# 06_ETHERNET.net
KiCad netlist of a schematic drawn in Altium Designer
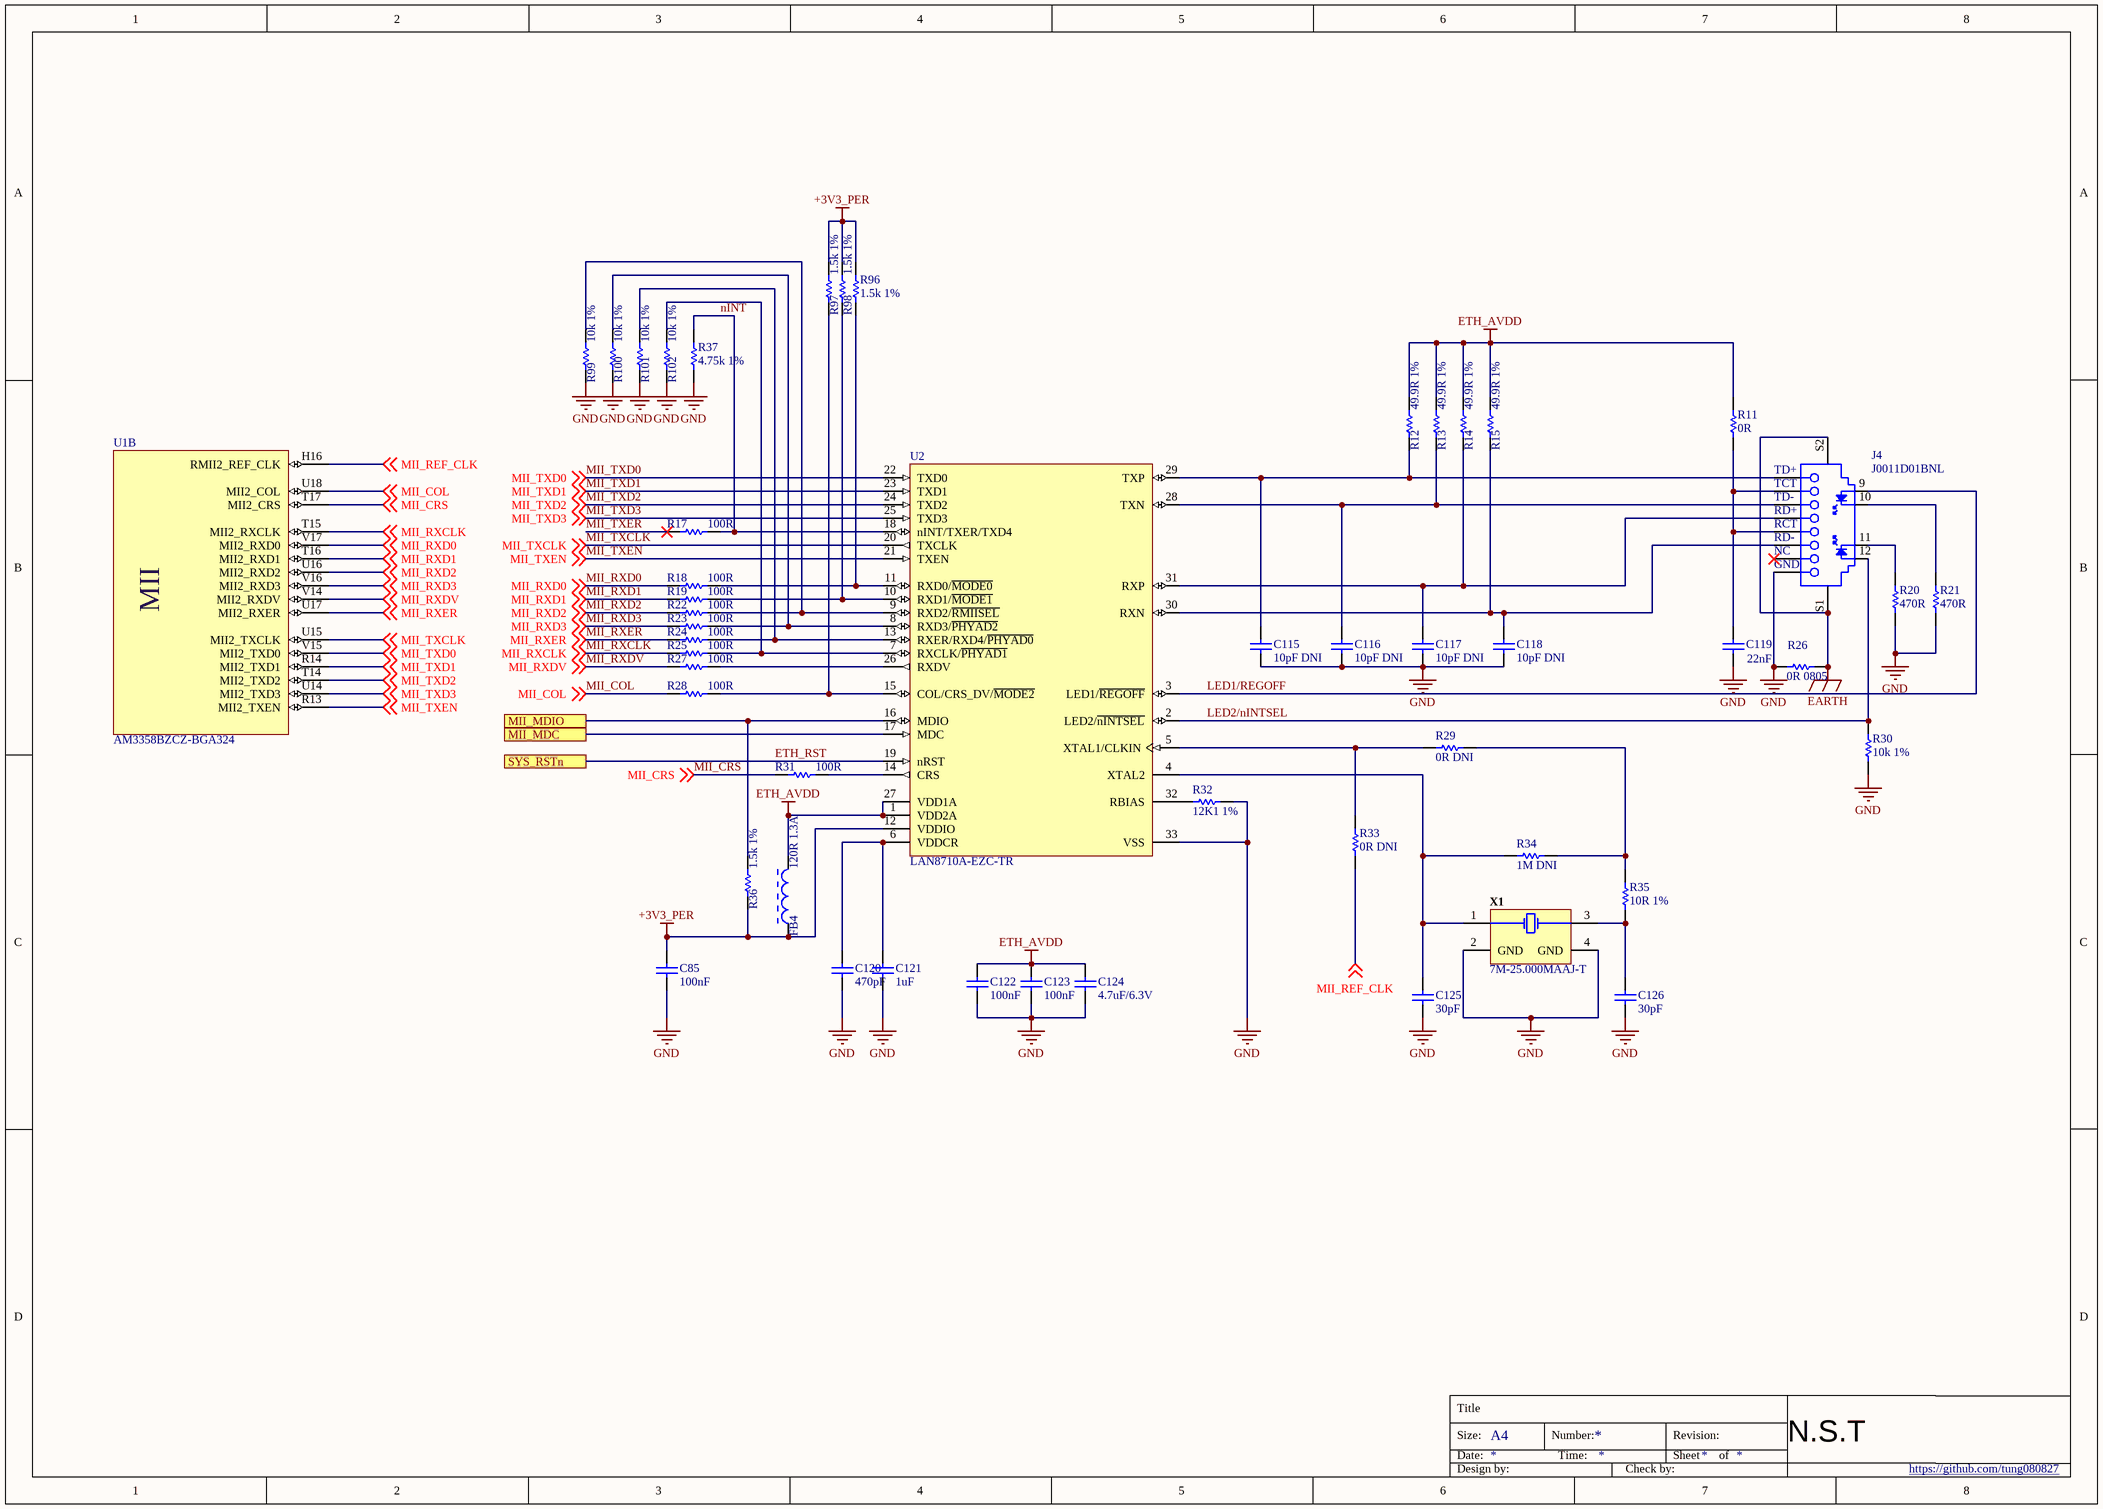
[diagram p0: 06. ETHERNET.SchDoc]

(export (version "E")
  (design (tool "Eeschema 10.0.6"))
  (components
    (comp (ref "C85")
      (value "100nF")
      (footprint "CAPC1005X60X30LL05T10")
      (description "Chip Capacitor, 0.1 uF, +/- 10%, 16 V, -55 to 125 degC, 0402 (1005 Metric), RoHS, Tape and Reel")
      (fields (field (name "VOLTAGE") "16V") (field (name "TOLERANCE") "10%"))
      (libsource (lib "AM3358_DEV_BOARD") (part "CAP-NP-2"))
    )
    (comp (ref "C115")
      (value "10pF DNI")
      (footprint "CAPC1005X60X30LL05T10")
      (fields (field (name "MANUFACTURER") "Murata") (field (name "PART NUMBER") "GRM1555C1E100JA01D"))
      (libsource (lib "AM3358_DEV_BOARD") (part "CAP"))
    )
    (comp (ref "C116")
      (value "10pF DNI")
      (footprint "CAPC1005X60X30LL05T10")
      (fields (field (name "MANUFACTURER") "Murata") (field (name "PART NUMBER") "GRM1555C1E100JA01D"))
      (libsource (lib "AM3358_DEV_BOARD") (part "CAP"))
    )
    (comp (ref "C117")
      (value "10pF DNI")
      (footprint "CAPC1005X60X30LL05T10")
      (fields (field (name "MANUFACTURER") "Murata") (field (name "PART NUMBER") "GRM1555C1E100JA01D"))
      (libsource (lib "AM3358_DEV_BOARD") (part "CAP"))
    )
    (comp (ref "C118")
      (value "10pF DNI")
      (footprint "CAPC1005X60X30LL05T10")
      (fields (field (name "MANUFACTURER") "Murata") (field (name "PART NUMBER") "GRM1555C1E100JA01D"))
      (libsource (lib "AM3358_DEV_BOARD") (part "CAP"))
    )
    (comp (ref "C119")
      (value "22nF")
      (footprint "CAPC1005X60X30LL05T10")
      (fields (field (name "PART NUMBER") "GRM155R71H223KA12D") (field (name "MANUFACTURER") "Murata"))
      (libsource (lib "AM3358_DEV_BOARD") (part "CAP"))
    )
    (comp (ref "C120")
      (value "470pF")
      (footprint "CAPC1005X60X30LL05T10")
      (description "CAP 470pF 50V ±10% 0402 (1005 Metric) Thickness 0.6mm SMD")
      (fields (field (name "TOLERANCE") "Â±10%"))
      (libsource (lib "AM3358_DEV_BOARD") (part "CAP"))
    )
    (comp (ref "C121")
      (value "1uF")
      (footprint "CAPC1005X55X25NL05T10")
      (fields (field (name "PART NUMBER") "GRM155R61A105KE15D") (field (name "MANUFACTURER") "Murata"))
      (libsource (lib "Altium Content Vault") (part "CAP"))
    )
    (comp (ref "C122")
      (value "100nF")
      (footprint "CAPC1005X60X30LL05T10")
      (description "Chip Capacitor, 0.1 uF, +/- 10%, 16 V, -55 to 125 degC, 0402 (1005 Metric), RoHS, Tape and Reel")
      (fields (field (name "VOLTAGE") "16V") (field (name "TOLERANCE") "10%"))
      (libsource (lib "AM3358_DEV_BOARD") (part "CAP-NP-2"))
    )
    (comp (ref "C123")
      (value "100nF")
      (footprint "CAPC1005X60X30LL05T10")
      (description "Chip Capacitor, 0.1 uF, +/- 10%, 16 V, -55 to 125 degC, 0402 (1005 Metric), RoHS, Tape and Reel")
      (fields (field (name "VOLTAGE") "16V") (field (name "TOLERANCE") "10%"))
      (libsource (lib "AM3358_DEV_BOARD") (part "CAP-NP-2"))
    )
    (comp (ref "C124")
      (value "4.7uF/6.3V")
      (footprint "CAPC1005X55X25NL05T10")
      (fields (field (name "PART NUMBER") "GRM155R60J475ME47D") (field (name "MANUFACTURER") "Murata"))
      (libsource (lib "Altium Content Vault") (part "CAP"))
    )
    (comp (ref "C125")
      (value "30pF")
      (footprint "CAPC1005X60X30LL05T10")
      (fields (field (name "PART NUMBER") "GRM1555C1H300JA01D") (field (name "MANUFACTURER") "Murata"))
      (libsource (lib "AM3358_DEV_BOARD") (part "CAP"))
    )
    (comp (ref "C126")
      (value "30pF")
      (footprint "CAPC1005X60X30LL05T10")
      (fields (field (name "PART NUMBER") "GRM1555C1H300JA01D") (field (name "MANUFACTURER") "Murata"))
      (libsource (lib "AM3358_DEV_BOARD") (part "CAP"))
    )
    (comp (ref "FB4")
      (value "120R 1.3A")
      (footprint "MURA-BLM15-CHIP-2_V")
      (fields (field (name "PARTNUMBER") "BLM15PD121SN1D") (field (name "MANUFACTURER") "Murata"))
      (libsource (lib "Altium Content Vault") (part "MURA-FB-2"))
    )
    (comp (ref "J4")
      (value "J0011D01BNL")
      (footprint "J0011D01BNL 1PORT 100 BASE-TX")
      (fields (field (name "MANUFACTURER") "Pulse Electronics"))
      (libsource (lib "AM3358_DEV_BOARD") (part "RJ45-12-2SHLD_F"))
    )
    (comp (ref "R11")
      (value "0R")
      (footprint "RESC1005X40X25LL05T05")
      (fields (field (name "PART NUMBER") "CRCW040210R0FKEDHP") (field (name "MANUFACTURER") "Vishay Dale"))
      (libsource (lib "AM3358_DEV_BOARD") (part "RES"))
    )
    (comp (ref "R12")
      (value "49.9R 1%")
      (footprint "RESC1005X40X25LL05T05")
      (description "Precision Thick Film Chip Resistors")
      (fields (field (name "MANUFACTURER") "Panasonic") (field (name "PART NUMBER") "ERJ-2RKF49R9X"))
      (libsource (lib "AM3358_DEV_BOARD") (part "RES"))
    )
    (comp (ref "R13")
      (value "49.9R 1%")
      (footprint "RESC1005X40X25LL05T05")
      (description "Precision Thick Film Chip Resistors")
      (fields (field (name "MANUFACTURER") "Panasonic") (field (name "PART NUMBER") "ERJ-2RKF49R9X"))
      (libsource (lib "AM3358_DEV_BOARD") (part "RES"))
    )
    (comp (ref "R14")
      (value "49.9R 1%")
      (footprint "RESC1005X40X25LL05T05")
      (description "Precision Thick Film Chip Resistors")
      (fields (field (name "MANUFACTURER") "Panasonic") (field (name "PART NUMBER") "ERJ-2RKF49R9X"))
      (libsource (lib "AM3358_DEV_BOARD") (part "RES"))
    )
    (comp (ref "R15")
      (value "49.9R 1%")
      (footprint "RESC1005X40X25LL05T05")
      (description "Precision Thick Film Chip Resistors")
      (fields (field (name "MANUFACTURER") "Panasonic") (field (name "PART NUMBER") "ERJ-2RKF49R9X"))
      (libsource (lib "AM3358_DEV_BOARD") (part "RES"))
    )
    (comp (ref "R17")
      (value "100R")
      (footprint "RESC1005X40X25LL05T05")
      (fields (field (name "MANUFACTURER") "Panasonic") (field (name "PART NUMBER") "ERJ-2GEJ101X"))
      (libsource (lib "AM3358_DEV_BOARD") (part "RES"))
    )
    (comp (ref "R18")
      (value "100R")
      (footprint "RESC1005X40X25LL05T05")
      (fields (field (name "MANUFACTURER") "Panasonic") (field (name "PART NUMBER") "ERJ-2GEJ101X"))
      (libsource (lib "AM3358_DEV_BOARD") (part "RES"))
    )
    (comp (ref "R19")
      (value "100R")
      (footprint "RESC1005X40X25LL05T05")
      (fields (field (name "MANUFACTURER") "Panasonic") (field (name "PART NUMBER") "ERJ-2GEJ101X"))
      (libsource (lib "AM3358_DEV_BOARD") (part "RES"))
    )
    (comp (ref "R20")
      (value "470R")
      (footprint "RESC1005X40X25LL05T05")
      (fields (field (name "PART NUMBER") "CRCW0603470RFKEA") (field (name "MANUFACTURER") "Vishay Dale"))
      (libsource (lib "AM3358_DEV_BOARD") (part "RES"))
    )
    (comp (ref "R21")
      (value "470R")
      (footprint "RESC1005X40X25LL05T05")
      (fields (field (name "PART NUMBER") "CRCW0603470RFKEA") (field (name "MANUFACTURER") "Vishay Dale"))
      (libsource (lib "AM3358_DEV_BOARD") (part "RES"))
    )
    (comp (ref "R22")
      (value "100R")
      (footprint "RESC1005X40X25LL05T05")
      (fields (field (name "MANUFACTURER") "Panasonic") (field (name "PART NUMBER") "ERJ-2GEJ101X"))
      (libsource (lib "AM3358_DEV_BOARD") (part "RES"))
    )
    (comp (ref "R23")
      (value "100R")
      (footprint "RESC1005X40X25LL05T05")
      (fields (field (name "MANUFACTURER") "Panasonic") (field (name "PART NUMBER") "ERJ-2GEJ101X"))
      (libsource (lib "AM3358_DEV_BOARD") (part "RES"))
    )
    (comp (ref "R24")
      (value "100R")
      (footprint "RESC1005X40X25LL05T05")
      (fields (field (name "MANUFACTURER") "Panasonic") (field (name "PART NUMBER") "ERJ-2GEJ101X"))
      (libsource (lib "AM3358_DEV_BOARD") (part "RES"))
    )
    (comp (ref "R25")
      (value "100R")
      (footprint "RESC1005X40X25LL05T05")
      (fields (field (name "MANUFACTURER") "Panasonic") (field (name "PART NUMBER") "ERJ-2GEJ101X"))
      (libsource (lib "AM3358_DEV_BOARD") (part "RES"))
    )
    (comp (ref "R26")
      (value "0R 0805")
      (footprint "RESC2013X50X30LL20T20")
      (fields (field (name "MANUFACTURER") "Vishay Dale") (field (name "PART NUMBER") "CRCW08050000Z0EA"))
      (libsource (lib "Altium Content Vault") (part "RES"))
    )
    (comp (ref "R27")
      (value "100R")
      (footprint "RESC1005X40X25LL05T05")
      (fields (field (name "MANUFACTURER") "Panasonic") (field (name "PART NUMBER") "ERJ-2GEJ101X"))
      (libsource (lib "AM3358_DEV_BOARD") (part "RES"))
    )
    (comp (ref "R28")
      (value "100R")
      (footprint "RESC1005X40X25LL05T05")
      (fields (field (name "MANUFACTURER") "Panasonic") (field (name "PART NUMBER") "ERJ-2GEJ101X"))
      (libsource (lib "AM3358_DEV_BOARD") (part "RES"))
    )
    (comp (ref "R29")
      (value "0R DNI")
      (footprint "RESC1005X40X25LL05T05")
      (fields (field (name "MANUFACTURER") "Yageo / Phycomp") (field (name "PART NUMBER") "RC0402JR-070RL"))
      (libsource (lib "AM3358_DEV_BOARD") (part "RES"))
    )
    (comp (ref "R30")
      (value "10k 1%")
      (footprint "RESC1005X40X25LL05T05")
      (fields (field (name "MANUFACTURER") "Vishay Dale") (field (name "PART NUMBER") "CRCW040210K0FKED"))
      (libsource (lib "AM3358_DEV_BOARD") (part "RES"))
    )
    (comp (ref "R31")
      (value "100R")
      (footprint "RESC1005X40X25LL05T05")
      (fields (field (name "MANUFACTURER") "Panasonic") (field (name "PART NUMBER") "ERJ-2GEJ101X"))
      (libsource (lib "AM3358_DEV_BOARD") (part "RES"))
    )
    (comp (ref "R32")
      (value "12K1 1%")
      (footprint "RESC1005X40X25LL05T05")
      (description "12K1 0.063W 1% 0402 (1005 Metric)  SMD")
      (fields (field (name "POWER") "0.063 W") (field (name "TOLERANCE") "1 %"))
      (libsource (lib "AM3358_DEV_BOARD") (part "RES"))
    )
    (comp (ref "R33")
      (value "0R DNI")
      (footprint "RESC1005X40X25LL05T05")
      (fields (field (name "MANUFACTURER") "Yageo / Phycomp") (field (name "PART NUMBER") "RC0402JR-070RL"))
      (libsource (lib "AM3358_DEV_BOARD") (part "RES"))
    )
    (comp (ref "R34")
      (value "1M DNI")
      (footprint "RESC1005X40X25LL05T05")
      (description "Chip Resistor, 1 MOhm, +/- 1%, 100 mW, -55 to 155 degC, 0402 (1005 Metric), RoHS, Tape and Reel")
      (fields (field (name "PARTNUMBER") "ERJ-2RKF1004X") (field (name "TOLERANCE") "1%"))
      (libsource (lib "AM3358_DEV_BOARD") (part "RES-2"))
    )
    (comp (ref "R35")
      (value "10R 1%")
      (footprint "RESC1005X40X25LL05T05")
      (fields (field (name "PART NUMBER") "CRCW040210R0FKEDHP") (field (name "MANUFACTURER") "Vishay Dale"))
      (libsource (lib "AM3358_DEV_BOARD") (part "RES"))
    )
    (comp (ref "R36")
      (value "1.5k 1%")
      (footprint "RESC1005X40X25LL05T05")
      (fields (field (name "MANUFACTURER") "Yageo") (field (name "PART NUMBER") "RT0402BRD071K5L"))
      (libsource (lib "AM3358_DEV_BOARD") (part "RES"))
    )
    (comp (ref "R37")
      (value "4.75k 1%")
      (footprint "RESC1005X40X25LL05T05")
      (fields (field (name "MANUFACTURER") "Vishay Dale") (field (name "PART NUMBER") "CRCW04024K75FKED"))
      (libsource (lib "AM3358_DEV_BOARD") (part "RES"))
    )
    (comp (ref "R96")
      (value "1.5k 1%")
      (footprint "RESC1005X40X25LL05T05")
      (fields (field (name "MANUFACTURER") "Yageo") (field (name "PART NUMBER") "RT0402BRD071K5L"))
      (libsource (lib "AM3358_DEV_BOARD") (part "RES"))
    )
    (comp (ref "R97")
      (value "1.5k 1%")
      (footprint "RESC1005X40X25LL05T05")
      (fields (field (name "MANUFACTURER") "Yageo") (field (name "PART NUMBER") "RT0402BRD071K5L"))
      (libsource (lib "AM3358_DEV_BOARD") (part "RES"))
    )
    (comp (ref "R98")
      (value "1.5k 1%")
      (footprint "RESC1005X40X25LL05T05")
      (fields (field (name "MANUFACTURER") "Yageo") (field (name "PART NUMBER") "RT0402BRD071K5L"))
      (libsource (lib "AM3358_DEV_BOARD") (part "RES"))
    )
    (comp (ref "R99")
      (value "10k 1%")
      (footprint "RESC1005X40X25LL05T05")
      (description "10k 0.063W 1% 0402 (1005 Metric)  SMD")
      (fields (field (name "MANUFACTURER") "Vishay Dale") (field (name "PART NUMBER") "CRCW040210K0FKED"))
      (libsource (lib "AM3358_DEV_BOARD") (part "RES"))
    )
    (comp (ref "R100")
      (value "10k 1%")
      (footprint "RESC1005X40X25LL05T05")
      (description "10k 0.063W 1% 0402 (1005 Metric)  SMD")
      (fields (field (name "MANUFACTURER") "Vishay Dale") (field (name "PART NUMBER") "CRCW040210K0FKED"))
      (libsource (lib "AM3358_DEV_BOARD") (part "RES"))
    )
    (comp (ref "R101")
      (value "10k 1%")
      (footprint "RESC1005X40X25LL05T05")
      (description "10k 0.063W 1% 0402 (1005 Metric)  SMD")
      (fields (field (name "MANUFACTURER") "Vishay Dale") (field (name "PART NUMBER") "CRCW040210K0FKED"))
      (libsource (lib "AM3358_DEV_BOARD") (part "RES"))
    )
    (comp (ref "R102")
      (value "10k 1%")
      (footprint "RESC1005X40X25LL05T05")
      (description "10k 0.063W 1% 0402 (1005 Metric)  SMD")
      (fields (field (name "MANUFACTURER") "Vishay Dale") (field (name "PART NUMBER") "CRCW040210K0FKED"))
      (libsource (lib "AM3358_DEV_BOARD") (part "RES"))
    )
    (comp (ref "U1")
      (value "AM3358BZCZ-BGA324")
      (footprint "TI-ZCZ324")
      (libsource (lib "SyTungNguyen") (part "AM3358BZCZ100"))
    )
    (comp (ref "U2")
      (value "LAN8710A-EZC-TR")
      (footprint "MCHP-QFN-32-5x5_V1")
      (fields (field (name "MANUFACTURER") "Microchip"))
      (libsource (lib "Altium Content Vault") (part "MCHP-LAN8710A-QFN-32"))
    )
    (comp (ref "X1")
      (value "7M-25.000MAAJ-T")
      (footprint "FP-NX3225SA-MFG")
      (fields (field (name "MANUFACTURER") "TXC"))
      (libsource (lib "AM3358_DEV_BOARD") (part "XTAL-1-3-4"))
    )
  )
  (nets
    (net (code "1") (name "+3V3_PER") (class "Default")
      (node (ref "C85") (pin "2") (pinfunction "2_2") (pintype "passive"))
      (node (ref "FB4") (pin "1") (pinfunction "1_1") (pintype "passive"))
      (node (ref "R36") (pin "1") (pinfunction "1_1") (pintype "passive"))
      (node (ref "R96") (pin "1") (pinfunction "1_1") (pintype "passive"))
      (node (ref "R97") (pin "2") (pinfunction "2_2") (pintype "passive"))
      (node (ref "R98") (pin "2") (pinfunction "2_2") (pintype "passive"))
      (node (ref "U2") (pin "12") (pinfunction "VDDIO_12") (pintype "power_in"))
    )
    (net (code "2") (name "/ETH_RST") (class "Default")
      (node (ref "U2") (pin "19") (pinfunction "nRST_19") (pintype "input"))
    )
    (net (code "3") (name "/LED1{slash}REGOFF") (class "Default")
      (node (ref "J4") (pin "9") (pinfunction "9_9") (pintype "passive"))
      (node (ref "U2") (pin "3") (pinfunction "LED1/~{REGOFF}_3") (pintype "bidirectional"))
    )
    (net (code "4") (name "/LED2{slash}nINTSEL") (class "Default")
      (node (ref "J4") (pin "12") (pinfunction "12_12") (pintype "passive"))
      (node (ref "R30") (pin "2") (pinfunction "2_2") (pintype "passive"))
      (node (ref "U2") (pin "2") (pinfunction "LED2/~{nINTSEL}_2") (pintype "bidirectional"))
    )
    (net (code "5") (name "/MII_MDC") (class "Default")
      (node (ref "U2") (pin "17") (pinfunction "MDC_17") (pintype "input"))
    )
    (net (code "6") (name "/MII_MDIO") (class "Default")
      (node (ref "R36") (pin "2") (pinfunction "2_2") (pintype "passive"))
      (node (ref "U2") (pin "16") (pinfunction "MDIO_16") (pintype "bidirectional"))
    )
    (net (code "7") (name "/MII_TXER") (class "Default")
      (node (ref "R17") (pin "1") (pinfunction "1_1") (pintype "passive+no_connect"))
    )
    (net (code "8") (name "/nINT") (class "Default")
      (node (ref "R17") (pin "2") (pinfunction "2_2") (pintype "passive"))
      (node (ref "R37") (pin "2") (pinfunction "2_2") (pintype "passive"))
      (node (ref "U2") (pin "18") (pinfunction "nINT/TXER/TXD4_18") (pintype "bidirectional"))
    )
    (net (code "9") (name "EARTH") (class "Default")
      (node (ref "J4") (pin "S1") (pinfunction "S1_S1") (pintype "passive"))
      (node (ref "J4") (pin "S2") (pinfunction "S2_S2") (pintype "passive"))
      (node (ref "R26") (pin "2") (pinfunction "2_2") (pintype "passive"))
    )
    (net (code "10") (name "ETH_AVDD") (class "Default")
      (node (ref "C122") (pin "2") (pinfunction "2_2") (pintype "passive"))
      (node (ref "C123") (pin "2") (pinfunction "2_2") (pintype "passive"))
      (node (ref "C124") (pin "2") (pinfunction "2_2") (pintype "passive"))
      (node (ref "FB4") (pin "2") (pinfunction "2_2") (pintype "passive"))
      (node (ref "R11") (pin "2") (pinfunction "2_2") (pintype "passive"))
      (node (ref "R12") (pin "2") (pinfunction "2_2") (pintype "passive"))
      (node (ref "R13") (pin "2") (pinfunction "2_2") (pintype "passive"))
      (node (ref "R14") (pin "2") (pinfunction "2_2") (pintype "passive"))
      (node (ref "R15") (pin "2") (pinfunction "2_2") (pintype "passive"))
      (node (ref "U2") (pin "1") (pinfunction "VDD2A_1") (pintype "power_in"))
      (node (ref "U2") (pin "27") (pinfunction "VDD1A_27") (pintype "power_in"))
    )
    (net (code "11") (name "GND") (class "Default")
      (node (ref "C115") (pin "1") (pinfunction "1_1") (pintype "passive"))
      (node (ref "C116") (pin "1") (pinfunction "1_1") (pintype "passive"))
      (node (ref "C117") (pin "1") (pinfunction "1_1") (pintype "passive"))
      (node (ref "C118") (pin "1") (pinfunction "1_1") (pintype "passive"))
      (node (ref "C119") (pin "1") (pinfunction "1_1") (pintype "passive"))
      (node (ref "C120") (pin "1") (pinfunction "1_1") (pintype "passive"))
      (node (ref "C121") (pin "1") (pinfunction "1_1") (pintype "passive"))
      (node (ref "C122") (pin "1") (pinfunction "1_1") (pintype "passive"))
      (node (ref "C123") (pin "1") (pinfunction "1_1") (pintype "passive"))
      (node (ref "C124") (pin "1") (pinfunction "1_1") (pintype "passive"))
      (node (ref "C125") (pin "1") (pinfunction "1_1") (pintype "passive"))
      (node (ref "C126") (pin "1") (pinfunction "1_1") (pintype "passive"))
      (node (ref "C85") (pin "1") (pinfunction "1_1") (pintype "passive"))
      (node (ref "J4") (pin "8") (pinfunction "GND_8") (pintype "passive"))
      (node (ref "R100") (pin "1") (pinfunction "1_1") (pintype "passive"))
      (node (ref "R101") (pin "1") (pinfunction "1_1") (pintype "passive"))
      (node (ref "R102") (pin "1") (pinfunction "1_1") (pintype "passive"))
      (node (ref "R20") (pin "1") (pinfunction "1_1") (pintype "passive"))
      (node (ref "R21") (pin "1") (pinfunction "1_1") (pintype "passive"))
      (node (ref "R26") (pin "1") (pinfunction "1_1") (pintype "passive"))
      (node (ref "R30") (pin "1") (pinfunction "1_1") (pintype "passive"))
      (node (ref "R32") (pin "2") (pinfunction "2_2") (pintype "passive"))
      (node (ref "R37") (pin "1") (pinfunction "1_1") (pintype "passive"))
      (node (ref "R99") (pin "1") (pinfunction "1_1") (pintype "passive"))
      (node (ref "U2") (pin "33") (pinfunction "VSS_33") (pintype "power_in"))
      (node (ref "X1") (pin "2") (pinfunction "GND_2") (pintype "power_in"))
      (node (ref "X1") (pin "4") (pinfunction "GND_4") (pintype "power_in"))
    )
    (net (code "12") (name "MII_COL") (class "Default")
      (node (ref "R28") (pin "1") (pinfunction "1_1") (pintype "passive"))
      (node (ref "U1") (pin "U18") (pinfunction "MII2_COL_U18") (pintype "bidirectional"))
    )
    (net (code "13") (name "MII_CRS") (class "Default")
      (node (ref "R31") (pin "1") (pinfunction "1_1") (pintype "passive"))
      (node (ref "U1") (pin "T17") (pinfunction "MII2_CRS_T17") (pintype "bidirectional"))
    )
    (net (code "14") (name "MII_REF_CLK") (class "Default")
      (node (ref "R33") (pin "1") (pinfunction "1_1") (pintype "passive"))
      (node (ref "U1") (pin "H16") (pinfunction "RMII2_REF_CLK_H16") (pintype "bidirectional"))
    )
    (net (code "15") (name "MII_RXCLK") (class "Default")
      (node (ref "R25") (pin "1") (pinfunction "1_1") (pintype "passive"))
      (node (ref "U1") (pin "T15") (pinfunction "MII2_RXCLK_T15") (pintype "bidirectional"))
    )
    (net (code "16") (name "MII_RXD0") (class "Default")
      (node (ref "R18") (pin "1") (pinfunction "1_1") (pintype "passive"))
      (node (ref "U1") (pin "V17") (pinfunction "MII2_RXD0_V17") (pintype "bidirectional"))
    )
    (net (code "17") (name "MII_RXD1") (class "Default")
      (node (ref "R19") (pin "1") (pinfunction "1_1") (pintype "passive"))
      (node (ref "U1") (pin "T16") (pinfunction "MII2_RXD1_T16") (pintype "bidirectional"))
    )
    (net (code "18") (name "MII_RXD2") (class "Default")
      (node (ref "R22") (pin "1") (pinfunction "1_1") (pintype "passive"))
      (node (ref "U1") (pin "U16") (pinfunction "MII2_RXD2_U16") (pintype "bidirectional"))
    )
    (net (code "19") (name "MII_RXD3") (class "Default")
      (node (ref "R23") (pin "1") (pinfunction "1_1") (pintype "passive"))
      (node (ref "U1") (pin "V16") (pinfunction "MII2_RXD3_V16") (pintype "bidirectional"))
    )
    (net (code "20") (name "MII_RXDV") (class "Default")
      (node (ref "R27") (pin "1") (pinfunction "1_1") (pintype "passive"))
      (node (ref "U1") (pin "V14") (pinfunction "MII2_RXDV_V14") (pintype "bidirectional"))
    )
    (net (code "21") (name "MII_RXER") (class "Default")
      (node (ref "R24") (pin "1") (pinfunction "1_1") (pintype "passive"))
      (node (ref "U1") (pin "U17") (pinfunction "MII2_RXER_U17") (pintype "bidirectional"))
    )
    (net (code "22") (name "MII_TXCLK") (class "Default")
      (node (ref "U1") (pin "U15") (pinfunction "MII2_TXCLK_U15") (pintype "bidirectional"))
      (node (ref "U2") (pin "20") (pinfunction "TXCLK_20") (pintype "output"))
    )
    (net (code "23") (name "MII_TXD0") (class "Default")
      (node (ref "U1") (pin "V15") (pinfunction "MII2_TXD0_V15") (pintype "bidirectional"))
      (node (ref "U2") (pin "22") (pinfunction "TXD0_22") (pintype "input"))
    )
    (net (code "24") (name "MII_TXD1") (class "Default")
      (node (ref "U1") (pin "R14") (pinfunction "MII2_TXD1_R14") (pintype "bidirectional"))
      (node (ref "U2") (pin "23") (pinfunction "TXD1_23") (pintype "input"))
    )
    (net (code "25") (name "MII_TXD2") (class "Default")
      (node (ref "U1") (pin "T14") (pinfunction "MII2_TXD2_T14") (pintype "bidirectional"))
      (node (ref "U2") (pin "24") (pinfunction "TXD2_24") (pintype "input"))
    )
    (net (code "26") (name "MII_TXD3") (class "Default")
      (node (ref "U1") (pin "U14") (pinfunction "MII2_TXD3_U14") (pintype "bidirectional"))
      (node (ref "U2") (pin "25") (pinfunction "TXD3_25") (pintype "input"))
    )
    (net (code "27") (name "MII_TXEN") (class "Default")
      (node (ref "U1") (pin "R13") (pinfunction "MII2_TXEN_R13") (pintype "bidirectional"))
      (node (ref "U2") (pin "21") (pinfunction "TXEN_21") (pintype "input"))
    )
    (net (code "28") (name "Net-(J4-Pad10)") (class "Default")
      (node (ref "J4") (pin "10") (pinfunction "10_10") (pintype "passive"))
      (node (ref "R21") (pin "2") (pinfunction "2_2") (pintype "passive"))
    )
    (net (code "29") (name "Net-(J4-Pad11)") (class "Default")
      (node (ref "J4") (pin "11") (pinfunction "11_11") (pintype "passive"))
      (node (ref "R20") (pin "2") (pinfunction "2_2") (pintype "passive"))
    )
    (net (code "30") (name "Net-(J4-RCT)") (class "Default")
      (node (ref "C119") (pin "2") (pinfunction "2_2") (pintype "passive"))
      (node (ref "J4") (pin "2") (pinfunction "TCT_2") (pintype "passive"))
      (node (ref "J4") (pin "5") (pinfunction "RCT_5") (pintype "passive"))
      (node (ref "R11") (pin "1") (pinfunction "1_1") (pintype "passive"))
    )
    (net (code "31") (name "Net-(J4-RD+)") (class "Default")
      (node (ref "C117") (pin "2") (pinfunction "2_2") (pintype "passive"))
      (node (ref "J4") (pin "4") (pinfunction "RD+_4") (pintype "passive"))
      (node (ref "R14") (pin "1") (pinfunction "1_1") (pintype "passive"))
      (node (ref "U2") (pin "31") (pinfunction "RXP_31") (pintype "bidirectional"))
    )
    (net (code "32") (name "Net-(J4-RD-)") (class "Default")
      (node (ref "C118") (pin "2") (pinfunction "2_2") (pintype "passive"))
      (node (ref "J4") (pin "6") (pinfunction "RD-_6") (pintype "passive"))
      (node (ref "R15") (pin "1") (pinfunction "1_1") (pintype "passive"))
      (node (ref "U2") (pin "30") (pinfunction "RXN_30") (pintype "bidirectional"))
    )
    (net (code "33") (name "Net-(J4-TD+)") (class "Default")
      (node (ref "C115") (pin "2") (pinfunction "2_2") (pintype "passive"))
      (node (ref "J4") (pin "1") (pinfunction "TD+_1") (pintype "passive"))
      (node (ref "R12") (pin "1") (pinfunction "1_1") (pintype "passive"))
      (node (ref "U2") (pin "29") (pinfunction "TXP_29") (pintype "bidirectional"))
    )
    (net (code "34") (name "Net-(J4-TD-)") (class "Default")
      (node (ref "C116") (pin "2") (pinfunction "2_2") (pintype "passive"))
      (node (ref "J4") (pin "3") (pinfunction "TD-_3") (pintype "passive"))
      (node (ref "R13") (pin "1") (pinfunction "1_1") (pintype "passive"))
      (node (ref "U2") (pin "28") (pinfunction "TXN_28") (pintype "bidirectional"))
    )
    (net (code "35") (name "Net-(R29-Pad2)") (class "Default")
      (node (ref "R29") (pin "2") (pinfunction "2_2") (pintype "passive"))
      (node (ref "R34") (pin "2") (pinfunction "2_2") (pintype "passive"))
      (node (ref "R35") (pin "2") (pinfunction "2_2") (pintype "passive"))
    )
    (net (code "36") (name "Net-(U2-COL{slash}CRS_DV{slash}~{MODE2})") (class "Default")
      (node (ref "R28") (pin "2") (pinfunction "2_2") (pintype "passive"))
      (node (ref "R97") (pin "1") (pinfunction "1_1") (pintype "passive"))
      (node (ref "U2") (pin "15") (pinfunction "COL/CRS_DV/~{MODE2}_15") (pintype "bidirectional"))
    )
    (net (code "37") (name "Net-(U2-CRS)") (class "Default")
      (node (ref "R31") (pin "2") (pinfunction "2_2") (pintype "passive"))
      (node (ref "U2") (pin "14") (pinfunction "CRS_14") (pintype "output"))
    )
    (net (code "38") (name "Net-(U2-RBIAS)") (class "Default")
      (node (ref "R32") (pin "1") (pinfunction "1_1") (pintype "passive"))
      (node (ref "U2") (pin "32") (pinfunction "RBIAS_32") (pintype "passive"))
    )
    (net (code "39") (name "Net-(U2-RXCLK{slash}~{PHYAD1})") (class "Default")
      (node (ref "R102") (pin "2") (pinfunction "2_2") (pintype "passive"))
      (node (ref "R25") (pin "2") (pinfunction "2_2") (pintype "passive"))
      (node (ref "U2") (pin "7") (pinfunction "RXCLK/~{PHYAD1}_7") (pintype "bidirectional"))
    )
    (net (code "40") (name "Net-(U2-RXD0{slash}~{MODE0})") (class "Default")
      (node (ref "R18") (pin "2") (pinfunction "2_2") (pintype "passive"))
      (node (ref "R96") (pin "2") (pinfunction "2_2") (pintype "passive"))
      (node (ref "U2") (pin "11") (pinfunction "RXD0/~{MODE0}_11") (pintype "bidirectional"))
    )
    (net (code "41") (name "Net-(U2-RXD1{slash}~{MODE1})") (class "Default")
      (node (ref "R19") (pin "2") (pinfunction "2_2") (pintype "passive"))
      (node (ref "R98") (pin "1") (pinfunction "1_1") (pintype "passive"))
      (node (ref "U2") (pin "10") (pinfunction "RXD1/~{MODE1}_10") (pintype "bidirectional"))
    )
    (net (code "42") (name "Net-(U2-RXD2{slash}~{RMIISEL})") (class "Default")
      (node (ref "R22") (pin "2") (pinfunction "2_2") (pintype "passive"))
      (node (ref "R99") (pin "2") (pinfunction "2_2") (pintype "passive"))
      (node (ref "U2") (pin "9") (pinfunction "RXD2/~{RMIISEL}_9") (pintype "bidirectional"))
    )
    (net (code "43") (name "Net-(U2-RXD3{slash}~{PHYAD2})") (class "Default")
      (node (ref "R100") (pin "2") (pinfunction "2_2") (pintype "passive"))
      (node (ref "R23") (pin "2") (pinfunction "2_2") (pintype "passive"))
      (node (ref "U2") (pin "8") (pinfunction "RXD3/~{PHYAD2}_8") (pintype "bidirectional"))
    )
    (net (code "44") (name "Net-(U2-RXDV)") (class "Default")
      (node (ref "R27") (pin "2") (pinfunction "2_2") (pintype "passive"))
      (node (ref "U2") (pin "26") (pinfunction "RXDV_26") (pintype "output"))
    )
    (net (code "45") (name "Net-(U2-RXER{slash}RXD4{slash}~{PHYAD0})") (class "Default")
      (node (ref "R101") (pin "2") (pinfunction "2_2") (pintype "passive"))
      (node (ref "R24") (pin "2") (pinfunction "2_2") (pintype "passive"))
      (node (ref "U2") (pin "13") (pinfunction "RXER/RXD4/~{PHYAD0}_13") (pintype "bidirectional"))
    )
    (net (code "46") (name "Net-(U2-VDDCR)") (class "Default")
      (node (ref "C120") (pin "2") (pinfunction "2_2") (pintype "passive"))
      (node (ref "C121") (pin "2") (pinfunction "2_2") (pintype "passive"))
      (node (ref "U2") (pin "6") (pinfunction "VDDCR_6") (pintype "power_in"))
    )
    (net (code "47") (name "Net-(U2-XTAL1{slash}CLKIN)") (class "Default")
      (node (ref "R29") (pin "1") (pinfunction "1_1") (pintype "passive"))
      (node (ref "R33") (pin "2") (pinfunction "2_2") (pintype "passive"))
      (node (ref "U2") (pin "5") (pinfunction "XTAL1/CLKIN_5") (pintype "input"))
    )
    (net (code "48") (name "Net-(U2-XTAL2)") (class "Default")
      (node (ref "C125") (pin "2") (pinfunction "2_2") (pintype "passive"))
      (node (ref "R34") (pin "1") (pinfunction "1_1") (pintype "passive"))
      (node (ref "U2") (pin "4") (pinfunction "XTAL2_4") (pintype "passive"))
      (node (ref "X1") (pin "1") (pinfunction "X1_1") (pintype "passive"))
    )
    (net (code "49") (name "Net-(X1-X2)") (class "Default")
      (node (ref "C126") (pin "2") (pinfunction "2_2") (pintype "passive"))
      (node (ref "R35") (pin "1") (pinfunction "1_1") (pintype "passive"))
      (node (ref "X1") (pin "3") (pinfunction "X2_3") (pintype "passive"))
    )
    (net (code "50") (name "unconnected-(J4-NC-Pad7)") (class "Default")
      (node (ref "J4") (pin "7") (pinfunction "NC_7") (pintype "passive+no_connect"))
    )
  )
)
